# KhoiPhu.net
KiCad netlist of a schematic drawn in Altium Designer
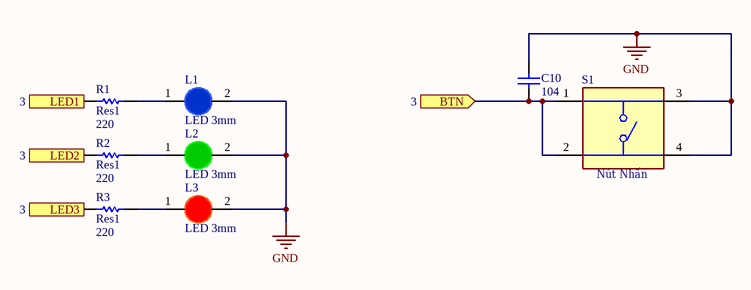
[diagram p0: KhoiPhu.SchDoc]

(export (version "E")
  (design (tool "Eeschema 10.0.6"))
  (components
    (comp (ref "C10")
      (value "104")
      (footprint "tu gom")
      (description "Cắm")
      (libsource (lib "Altium_Lib_by_KhueNguyenCreator") (part "Tu gom 104 50V"))
    )
    (comp (ref "L1")
      (value "LED 3mm")
      (footprint "LED-3MM-BLUE")
      (description "Cắm")
      (libsource (lib "Altium_Lib_by_KhueNguyenCreator") (part "LED 3mm Xanh Duong"))
    )
    (comp (ref "L2")
      (value "LED 3mm")
      (footprint "LED-3MM-GREEN")
      (description "Cắm")
      (libsource (lib "Altium_Lib_by_KhueNguyenCreator") (part "LED 3mm Xanh La"))
    )
    (comp (ref "L3")
      (value "LED 3mm")
      (footprint "LED-3MM-RED")
      (description "Cắm")
      (libsource (lib "Altium_Lib_by_KhueNguyenCreator") (part "LED 3mm Do"))
    )
    (comp (ref "R1")
      (value "Res1")
      (footprint "AXIAL-0.3")
      (description "Resistor")
      (fields (field (name "ALTIUM_VALUE") "220") (field (name "PUBLISHER") "Altium Limited"))
      (libsource (lib "Miscellaneous Devices") (part "Res1"))
    )
    (comp (ref "R2")
      (value "Res1")
      (footprint "AXIAL-0.3")
      (description "Resistor")
      (fields (field (name "ALTIUM_VALUE") "220") (field (name "PUBLISHER") "Altium Limited"))
      (libsource (lib "Miscellaneous Devices") (part "Res1"))
    )
    (comp (ref "R3")
      (value "Res1")
      (footprint "AXIAL-0.3")
      (description "Resistor")
      (fields (field (name "ALTIUM_VALUE") "220") (field (name "PUBLISHER") "Altium Limited"))
      (libsource (lib "Miscellaneous Devices") (part "Res1"))
    )
    (comp (ref "S1")
      (value "Nút Nhấn")
      (footprint "SW_TS04-66-95-BK-100-SMT")
      (description "6 x 6 mm, 9.5 mm Actuator Height, 100 gf, Black, Surface Mount, SPST, Tactile Switch")
      (fields (field (name "MF") "Same Sky") (field (name "MP") "TS04-66-95-BK-100-SMT"))
      (libsource (lib "nut nhan") (part "TS04-66-95-BK-100-SMT"))
    )
  )
  (nets
    (net (code "1") (name "/BTN") (class "Default")
      (node (ref "C10") (pin "2") (pinfunction "2_2") (pintype "passive"))
      (node (ref "S1") (pin "1") (pinfunction "1_1") (pintype "passive"))
      (node (ref "S1") (pin "2") (pinfunction "2_2") (pintype "passive"))
    )
    (net (code "2") (name "/LED1") (class "Default")
      (node (ref "R1") (pin "1") (pinfunction "1_1") (pintype "passive"))
    )
    (net (code "3") (name "/LED2") (class "Default")
      (node (ref "R2") (pin "1") (pinfunction "1_1") (pintype "passive"))
    )
    (net (code "4") (name "/LED3") (class "Default")
      (node (ref "R3") (pin "1") (pinfunction "1_1") (pintype "passive"))
    )
    (net (code "5") (name "GND") (class "Default")
      (node (ref "C10") (pin "1") (pinfunction "1_1") (pintype "passive"))
      (node (ref "L1") (pin "2") (pinfunction "K_2") (pintype "passive"))
      (node (ref "L2") (pin "2") (pinfunction "K_2") (pintype "passive"))
      (node (ref "L3") (pin "2") (pinfunction "K_2") (pintype "passive"))
      (node (ref "S1") (pin "3") (pinfunction "3_3") (pintype "passive"))
      (node (ref "S1") (pin "4") (pinfunction "4_4") (pintype "passive"))
    )
    (net (code "6") (name "Net-(L1-A)") (class "Default")
      (node (ref "L1") (pin "1") (pinfunction "A_1") (pintype "passive"))
      (node (ref "R1") (pin "2") (pinfunction "2_2") (pintype "passive"))
    )
    (net (code "7") (name "Net-(L2-A)") (class "Default")
      (node (ref "L2") (pin "1") (pinfunction "A_1") (pintype "passive"))
      (node (ref "R2") (pin "2") (pinfunction "2_2") (pintype "passive"))
    )
    (net (code "8") (name "Net-(L3-A)") (class "Default")
      (node (ref "L3") (pin "1") (pinfunction "A_1") (pintype "passive"))
      (node (ref "R3") (pin "2") (pinfunction "2_2") (pintype "passive"))
    )
  )
)
